# ProPrj_Bias-elimination-final.net
KiCad netlist of a schematic drawn in EasyEDA Pro
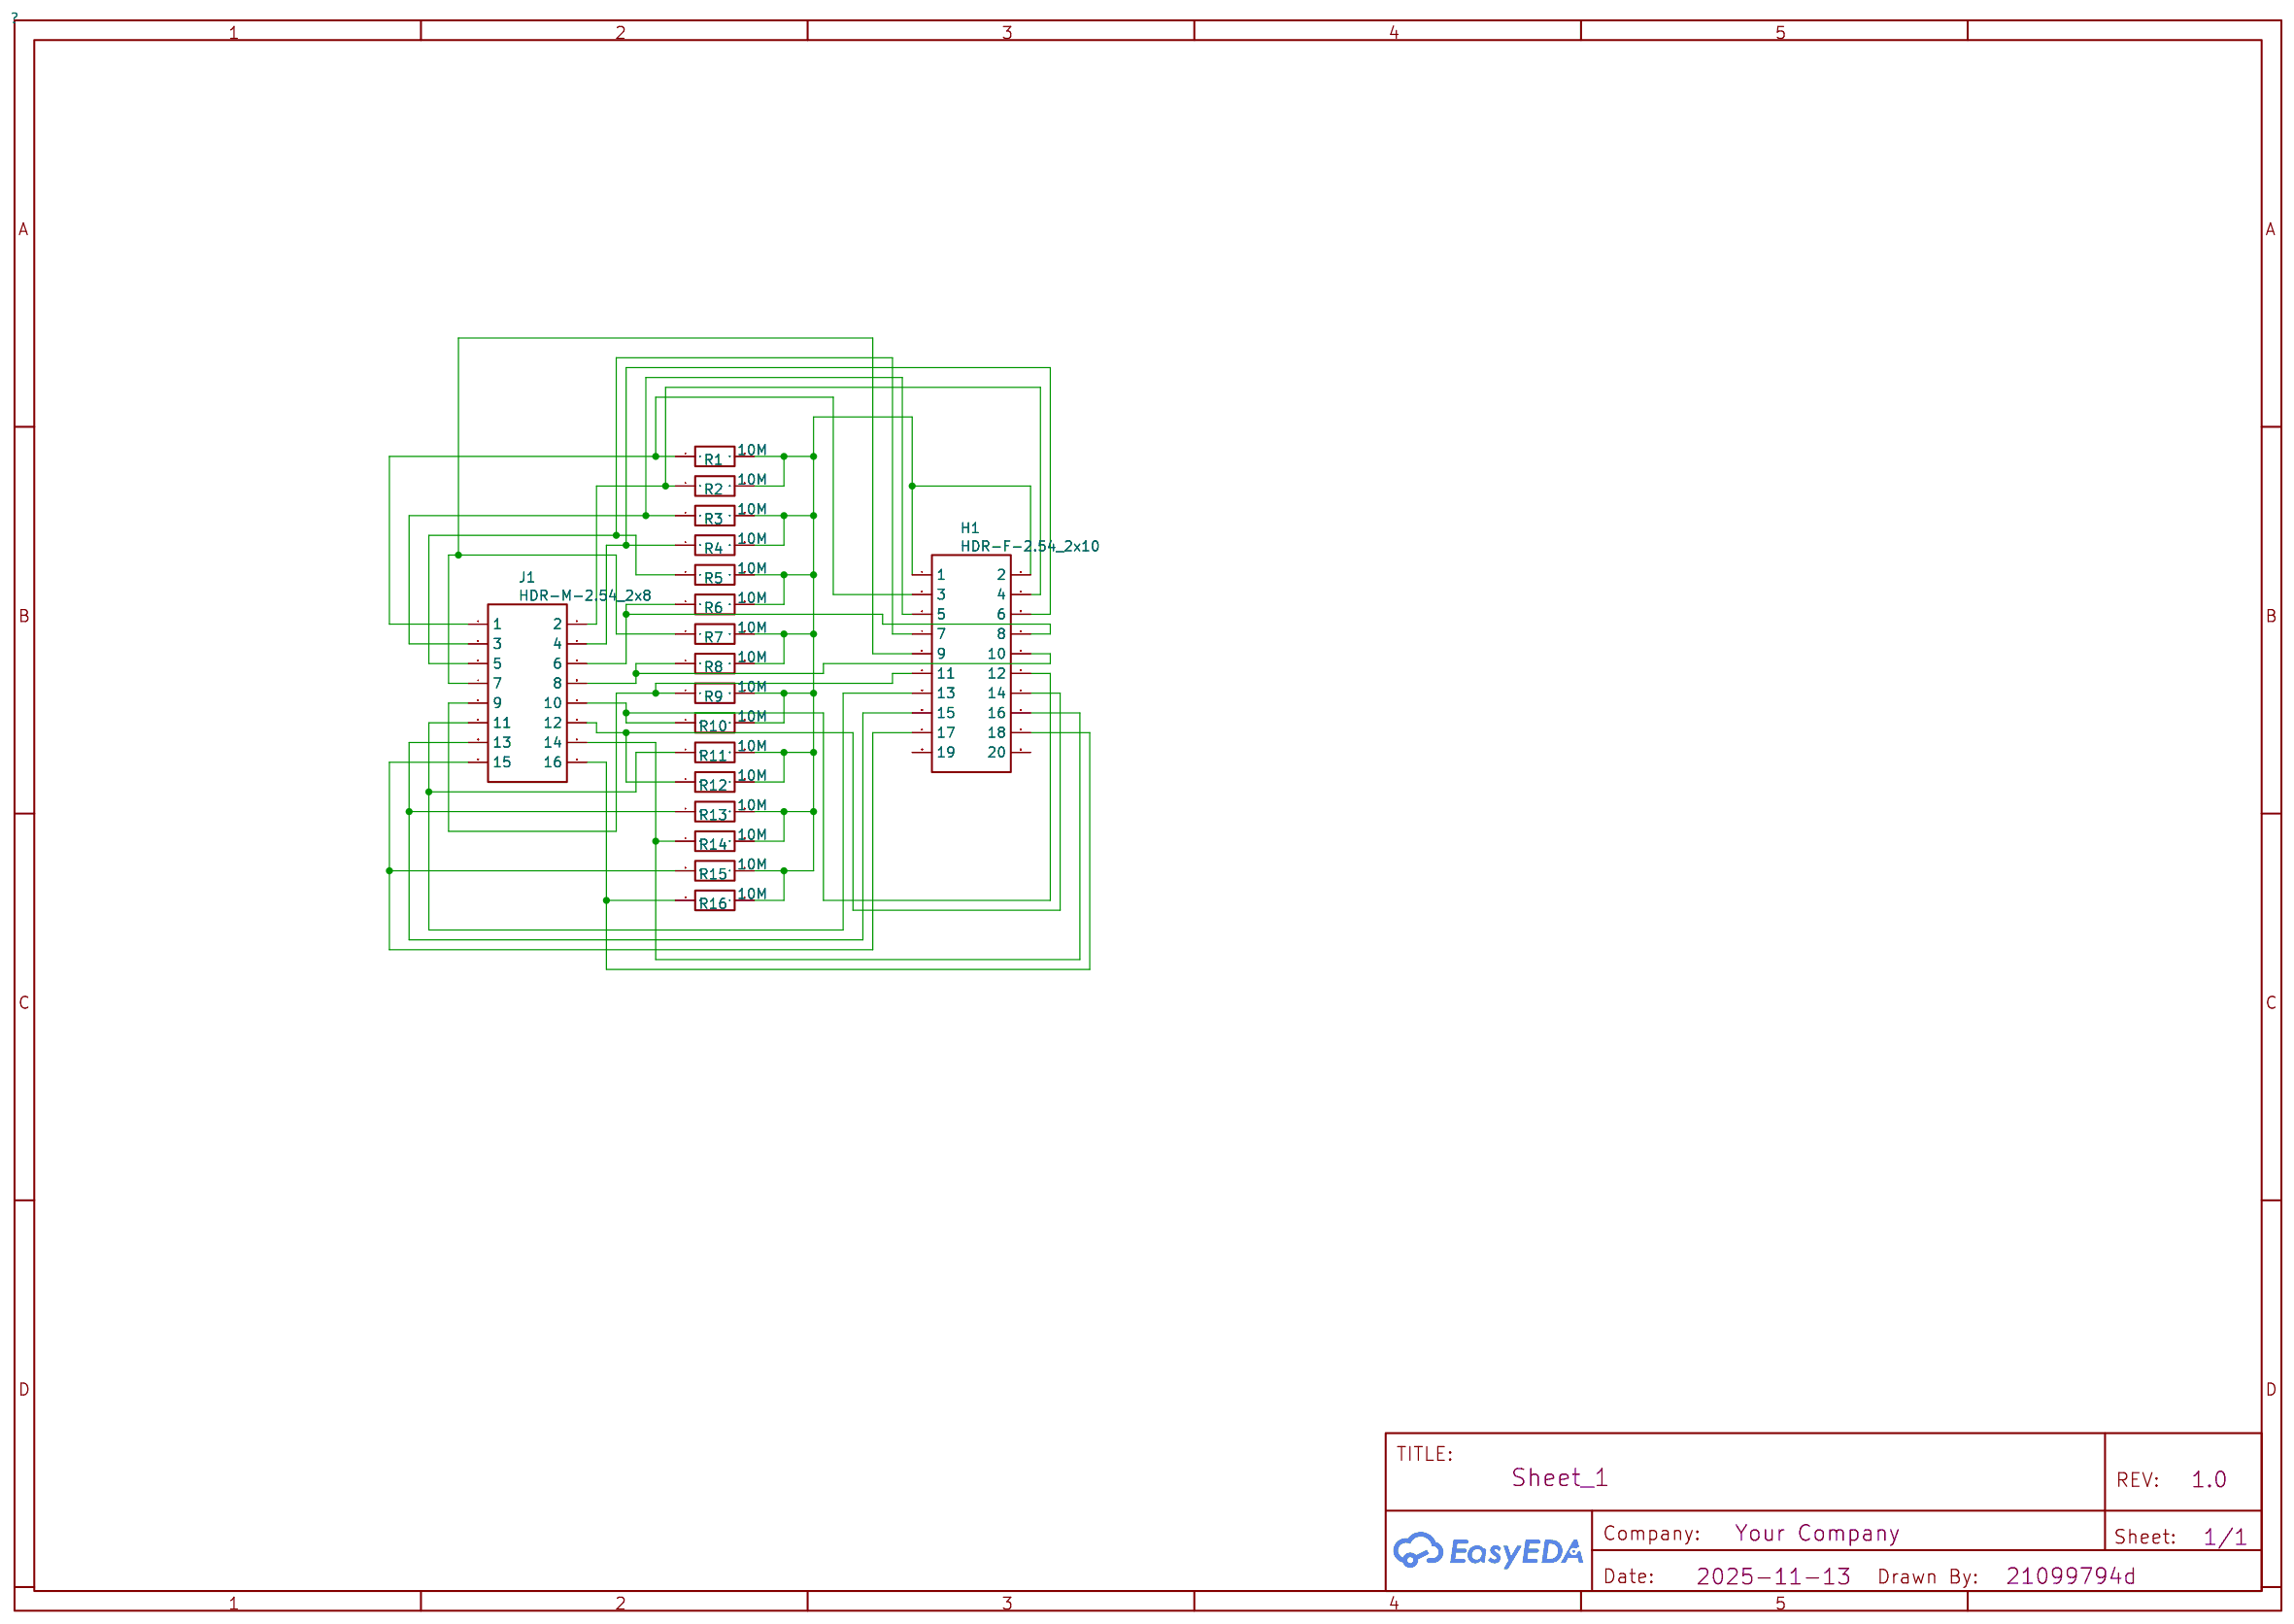
[diagram p0: schematic sheet]

(export (version "E")
  (design (tool "Eeschema 10.0.6"))
  (components
    (comp (ref "H1")
      (value "HDR-F-2.54_2x10")
      (footprint "easyedapro:HDR-F-2.54_2X10")
      (fields (field (name "Contributor") "LCEDA_Lib"))
      (libsource (lib "easyedapro") (part "HDR-F-2.54_2x10"))
    )
    (comp (ref "J1")
      (value "HDR-M-2.54_2x8")
      (footprint "easyedapro:HDR-M-2.54_2X8")
      (fields (field (name "Contributor") "LCEDA_Lib"))
      (libsource (lib "easyedapro") (part "HDR-M-2.54_2x8"))
    )
    (comp (ref "R1")
      (value "10M")
      (footprint "easyedapro:R0603")
      (fields (field (name "Contributor") "LCEDA_Lib"))
      (libsource (lib "easyedapro") (part "10M"))
    )
    (comp (ref "R2")
      (value "10M")
      (footprint "easyedapro:R0603")
      (fields (field (name "Contributor") "LCEDA_Lib"))
      (libsource (lib "easyedapro") (part "10M"))
    )
    (comp (ref "R3")
      (value "10M")
      (footprint "easyedapro:R0603")
      (fields (field (name "Contributor") "LCEDA_Lib"))
      (libsource (lib "easyedapro") (part "10M"))
    )
    (comp (ref "R4")
      (value "10M")
      (footprint "easyedapro:R0603")
      (fields (field (name "Contributor") "LCEDA_Lib"))
      (libsource (lib "easyedapro") (part "10M"))
    )
    (comp (ref "R5")
      (value "10M")
      (footprint "easyedapro:R0603")
      (fields (field (name "Contributor") "LCEDA_Lib"))
      (libsource (lib "easyedapro") (part "10M"))
    )
    (comp (ref "R6")
      (value "10M")
      (footprint "easyedapro:R0603")
      (fields (field (name "Contributor") "LCEDA_Lib"))
      (libsource (lib "easyedapro") (part "10M"))
    )
    (comp (ref "R7")
      (value "10M")
      (footprint "easyedapro:R0603")
      (fields (field (name "Contributor") "LCEDA_Lib"))
      (libsource (lib "easyedapro") (part "10M"))
    )
    (comp (ref "R8")
      (value "10M")
      (footprint "easyedapro:R0603")
      (fields (field (name "Contributor") "LCEDA_Lib"))
      (libsource (lib "easyedapro") (part "10M"))
    )
    (comp (ref "R9")
      (value "10M")
      (footprint "easyedapro:R0603")
      (fields (field (name "Contributor") "LCEDA_Lib"))
      (libsource (lib "easyedapro") (part "10M"))
    )
    (comp (ref "R10")
      (value "10M")
      (footprint "easyedapro:R0603")
      (fields (field (name "Contributor") "LCEDA_Lib"))
      (libsource (lib "easyedapro") (part "10M"))
    )
    (comp (ref "R11")
      (value "10M")
      (footprint "easyedapro:R0603")
      (fields (field (name "Contributor") "LCEDA_Lib"))
      (libsource (lib "easyedapro") (part "10M"))
    )
    (comp (ref "R12")
      (value "10M")
      (footprint "easyedapro:R0603")
      (fields (field (name "Contributor") "LCEDA_Lib"))
      (libsource (lib "easyedapro") (part "10M"))
    )
    (comp (ref "R13")
      (value "10M")
      (footprint "easyedapro:R0603")
      (fields (field (name "Contributor") "LCEDA_Lib"))
      (libsource (lib "easyedapro") (part "10M"))
    )
    (comp (ref "R14")
      (value "10M")
      (footprint "easyedapro:R0603")
      (fields (field (name "Contributor") "LCEDA_Lib"))
      (libsource (lib "easyedapro") (part "10M"))
    )
    (comp (ref "R15")
      (value "10M")
      (footprint "easyedapro:R0603")
      (fields (field (name "Contributor") "LCEDA_Lib"))
      (libsource (lib "") (part "10M_1"))
    )
    (comp (ref "R16")
      (value "10M")
      (footprint "easyedapro:R0603")
      (fields (field (name "Contributor") "LCEDA_Lib"))
      (libsource (lib "") (part "10M_1"))
    )
  )
  (nets
    (net (code "1") (name "Net-(H1-Pad1)") (class "Default")
      (node (ref "H1") (pin "1") (pinfunction "1_1") (pintype "input"))
      (node (ref "H1") (pin "2") (pinfunction "2_2") (pintype "input"))
      (node (ref "R1") (pin "2") (pinfunction "2_2") (pintype "unspecified"))
      (node (ref "R10") (pin "2") (pinfunction "2_2") (pintype "unspecified"))
      (node (ref "R11") (pin "2") (pinfunction "2_2") (pintype "unspecified"))
      (node (ref "R12") (pin "2") (pinfunction "2_2") (pintype "unspecified"))
      (node (ref "R13") (pin "2") (pinfunction "2_2") (pintype "unspecified"))
      (node (ref "R14") (pin "2") (pinfunction "2_2") (pintype "unspecified"))
      (node (ref "R15") (pin "1") (pinfunction "1_1") (pintype "unspecified"))
      (node (ref "R16") (pin "1") (pinfunction "1_1") (pintype "unspecified"))
      (node (ref "R2") (pin "2") (pinfunction "2_2") (pintype "unspecified"))
      (node (ref "R3") (pin "2") (pinfunction "2_2") (pintype "unspecified"))
      (node (ref "R4") (pin "2") (pinfunction "2_2") (pintype "unspecified"))
      (node (ref "R5") (pin "2") (pinfunction "2_2") (pintype "unspecified"))
      (node (ref "R6") (pin "2") (pinfunction "2_2") (pintype "unspecified"))
      (node (ref "R7") (pin "2") (pinfunction "2_2") (pintype "unspecified"))
      (node (ref "R8") (pin "2") (pinfunction "2_2") (pintype "unspecified"))
      (node (ref "R9") (pin "2") (pinfunction "2_2") (pintype "unspecified"))
    )
    (net (code "2") (name "Net-(H1-Pad3)") (class "Default")
      (node (ref "H1") (pin "3") (pinfunction "3_3") (pintype "input"))
      (node (ref "J1") (pin "1") (pinfunction "1_1") (pintype "input"))
      (node (ref "R1") (pin "1") (pinfunction "1_1") (pintype "unspecified"))
    )
    (net (code "3") (name "Net-(H1-Pad4)") (class "Default")
      (node (ref "H1") (pin "4") (pinfunction "4_4") (pintype "input"))
      (node (ref "J1") (pin "2") (pinfunction "2_2") (pintype "input"))
      (node (ref "R2") (pin "1") (pinfunction "1_1") (pintype "unspecified"))
    )
    (net (code "4") (name "Net-(H1-Pad5)") (class "Default")
      (node (ref "H1") (pin "5") (pinfunction "5_5") (pintype "input"))
      (node (ref "J1") (pin "3") (pinfunction "3_3") (pintype "input"))
      (node (ref "R3") (pin "1") (pinfunction "1_1") (pintype "unspecified"))
    )
    (net (code "5") (name "Net-(H1-Pad6)") (class "Default")
      (node (ref "H1") (pin "6") (pinfunction "6_6") (pintype "input"))
      (node (ref "J1") (pin "4") (pinfunction "4_4") (pintype "input"))
      (node (ref "R4") (pin "1") (pinfunction "1_1") (pintype "unspecified"))
    )
    (net (code "6") (name "Net-(H1-Pad7)") (class "Default")
      (node (ref "H1") (pin "7") (pinfunction "7_7") (pintype "input"))
      (node (ref "J1") (pin "5") (pinfunction "5_5") (pintype "input"))
      (node (ref "R5") (pin "1") (pinfunction "1_1") (pintype "unspecified"))
    )
    (net (code "7") (name "Net-(H1-Pad8)") (class "Default")
      (node (ref "H1") (pin "8") (pinfunction "8_8") (pintype "input"))
      (node (ref "J1") (pin "6") (pinfunction "6_6") (pintype "input"))
      (node (ref "R6") (pin "1") (pinfunction "1_1") (pintype "unspecified"))
    )
    (net (code "8") (name "Net-(H1-Pad9)") (class "Default")
      (node (ref "H1") (pin "9") (pinfunction "9_9") (pintype "input"))
      (node (ref "J1") (pin "7") (pinfunction "7_7") (pintype "input"))
      (node (ref "R7") (pin "1") (pinfunction "1_1") (pintype "unspecified"))
    )
    (net (code "9") (name "Net-(H1-Pad10)") (class "Default")
      (node (ref "H1") (pin "10") (pinfunction "10_10") (pintype "input"))
      (node (ref "J1") (pin "8") (pinfunction "8_8") (pintype "input"))
      (node (ref "R8") (pin "1") (pinfunction "1_1") (pintype "unspecified"))
    )
    (net (code "10") (name "Net-(H1-Pad11)") (class "Default")
      (node (ref "H1") (pin "11") (pinfunction "11_11") (pintype "input"))
      (node (ref "J1") (pin "9") (pinfunction "9_9") (pintype "input"))
      (node (ref "R9") (pin "1") (pinfunction "1_1") (pintype "unspecified"))
    )
    (net (code "11") (name "Net-(H1-Pad12)") (class "Default")
      (node (ref "H1") (pin "12") (pinfunction "12_12") (pintype "input"))
      (node (ref "J1") (pin "10") (pinfunction "10_10") (pintype "input"))
      (node (ref "R10") (pin "1") (pinfunction "1_1") (pintype "unspecified"))
    )
    (net (code "12") (name "Net-(H1-Pad13)") (class "Default")
      (node (ref "H1") (pin "13") (pinfunction "13_13") (pintype "input"))
      (node (ref "J1") (pin "11") (pinfunction "11_11") (pintype "input"))
      (node (ref "R11") (pin "1") (pinfunction "1_1") (pintype "unspecified"))
    )
    (net (code "13") (name "Net-(H1-Pad14)") (class "Default")
      (node (ref "H1") (pin "14") (pinfunction "14_14") (pintype "input"))
      (node (ref "J1") (pin "12") (pinfunction "12_12") (pintype "input"))
      (node (ref "R12") (pin "1") (pinfunction "1_1") (pintype "unspecified"))
    )
    (net (code "14") (name "Net-(H1-Pad15)") (class "Default")
      (node (ref "H1") (pin "15") (pinfunction "15_15") (pintype "input"))
      (node (ref "J1") (pin "13") (pinfunction "13_13") (pintype "input"))
      (node (ref "R13") (pin "1") (pinfunction "1_1") (pintype "unspecified"))
    )
    (net (code "15") (name "Net-(H1-Pad16)") (class "Default")
      (node (ref "H1") (pin "16") (pinfunction "16_16") (pintype "input"))
      (node (ref "J1") (pin "14") (pinfunction "14_14") (pintype "input"))
      (node (ref "R14") (pin "1") (pinfunction "1_1") (pintype "unspecified"))
    )
    (net (code "16") (name "Net-(H1-Pad17)") (class "Default")
      (node (ref "H1") (pin "17") (pinfunction "17_17") (pintype "input"))
      (node (ref "J1") (pin "15") (pinfunction "15_15") (pintype "input"))
      (node (ref "R15") (pin "2") (pinfunction "2_2") (pintype "unspecified"))
    )
    (net (code "17") (name "Net-(H1-Pad18)") (class "Default")
      (node (ref "H1") (pin "18") (pinfunction "18_18") (pintype "input"))
      (node (ref "J1") (pin "16") (pinfunction "16_16") (pintype "input"))
      (node (ref "R16") (pin "2") (pinfunction "2_2") (pintype "unspecified"))
    )
    (net (code "18") (name "unconnected-(H1-Pad19)") (class "Default")
      (node (ref "H1") (pin "19") (pinfunction "19_19") (pintype "input"))
    )
    (net (code "19") (name "unconnected-(H1-Pad20)") (class "Default")
      (node (ref "H1") (pin "20") (pinfunction "20_20") (pintype "input"))
    )
  )
)
